# Sheet3.net
KiCad netlist of a schematic drawn in Altium Designer
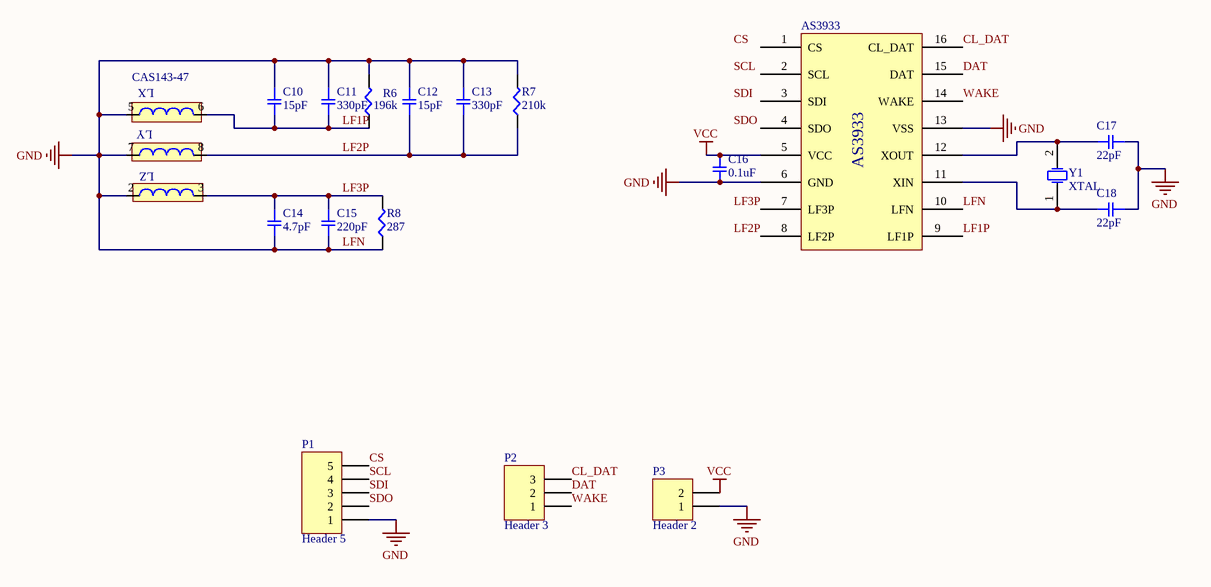
[diagram p0: Sheet3.SchDoc]

(export (version "E")
  (design (tool "Eeschema 10.0.6"))
  (components
    (comp (ref "AS3933")
      (value "~")
      (footprint "TSOP65P640X110-16N")
      (libsource (lib "AS3933") (part "Component_1"))
    )
    (comp (ref "C10")
      (value "15pF")
      (footprint "SMD-0805C")
      (description "Cap Ceramic 15pF 50V C0G 1%  0805")
      (fields (field (name "PART NUMBER") "CC0805FRNPO9BN150") (field (name "MANUFACTURER") "Yaego"))
      (libsource (lib "capacitor_0805") (part "CC0805FRNPO9BN150"))
    )
    (comp (ref "C11")
      (value "330pF")
      (footprint "SMD-0805C")
      (description "Cap Ceramic 330pF 50V C0G 2%  0805")
      (fields (field (name "PART NUMBER") "CC0805GRNPO9BN331") (field (name "MANUFACTURER") "Yageo"))
      (libsource (lib "capacitor_0805") (part "CC0805GRNPO9BN331"))
    )
    (comp (ref "C12")
      (value "15pF")
      (footprint "SMD-0805C")
      (description "Cap Ceramic 15pF 50V C0G 1%  0805")
      (fields (field (name "PART NUMBER") "CC0805FRNPO9BN150") (field (name "MANUFACTURER") "Yaego"))
      (libsource (lib "capacitor_0805") (part "CC0805FRNPO9BN150"))
    )
    (comp (ref "C13")
      (value "330pF")
      (footprint "SMD-0805C")
      (description "Cap Ceramic 330pF 50V C0G 2%  0805")
      (fields (field (name "PART NUMBER") "CC0805GRNPO9BN331") (field (name "MANUFACTURER") "Yageo"))
      (libsource (lib "capacitor_0805") (part "CC0805GRNPO9BN331"))
    )
    (comp (ref "C14")
      (value "4.7pF")
      (footprint "SMD-0805C")
      (description "Cap Ceramic 4.7pF 50V C0G 0.1pF  0805")
      (fields
        (field (name "PART NUMBER") "CL21C4R7BBANNNC")
        (field (name "MANUFACTURER") "Samsung Electro-Mechanics")
      )
      (libsource (lib "capacitor_0805") (part "CL21C4R7BBANNNC"))
    )
    (comp (ref "C15")
      (value "220pF")
      (footprint "SMD-0805C")
      (description "Cap Ceramic 220pF 100V C0G 1% 0805")
      (fields
        (field (name "PART NUMBER") "GCM2165C2A221FA16D")
        (field (name "MANUFACTURER") "Murata Manufacturing")
      )
      (libsource (lib "capacitor_0805") (part "GCM2165C2A221FA16D"))
    )
    (comp (ref "C16")
      (value "0.1uF")
      (footprint "SMD-0805C")
      (description "CAP CER 0.1uF 50V X7T 0805")
      (fields
        (field (name "PART NUMBER") "GC321AD72E103KX01D")
        (field (name "MANUFACTURER") "Samsung Electro-Mechanics")
      )
      (libsource (lib "capacitor_0805") (part "CL21B104JBCNNNC"))
    )
    (comp (ref "C17")
      (value "22pF")
      (footprint "SMD-0805C")
      (description "Cap Ceramic 22pF 50V C0G 5%0805")
      (fields
        (field (name "PART NUMBER") "CL21C220JBANNND")
        (field (name "MANUFACTURER") "Samsung Electro-Mechanics")
      )
      (libsource (lib "capacitor_0805") (part "CL21C220JBANNND"))
    )
    (comp (ref "C18")
      (value "22pF")
      (footprint "SMD-0805C")
      (description "Cap Ceramic 22pF 50V C0G 5%0805")
      (fields
        (field (name "PART NUMBER") "CL21C220JBANNND")
        (field (name "MANUFACTURER") "Samsung Electro-Mechanics")
      )
      (libsource (lib "capacitor_0805") (part "CL21C220JBANNND"))
    )
    (comp (ref "CAS143-47")
      (value "CAS143-47")
      (footprint "CAS143-47")
      (libsource (lib "CAS143-47") (part "Component_1"))
    )
    (comp (ref "P1")
      (value "Header 5")
      (footprint "HDR1X5")
      (description "Header, 5-Pin")
      (fields (field (name "PUBLISHER") "Altium Limited"))
      (libsource (lib "Miscellaneous Connectors") (part "Header 5"))
    )
    (comp (ref "P2")
      (value "Header 3")
      (footprint "HDR1X3")
      (description "Header, 3-Pin")
      (fields (field (name "PUBLISHER") "Altium Limited"))
      (libsource (lib "Miscellaneous Connectors") (part "Header 3"))
    )
    (comp (ref "P3")
      (value "Header 2")
      (footprint "HDR1X2")
      (description "Header, 2-Pin")
      (fields (field (name "PUBLISHER") "Altium Limited"))
      (libsource (lib "Miscellaneous Connectors") (part "Header 2"))
    )
    (comp (ref "R6")
      (value "196k")
      (footprint "SMD-0805-RES")
      (description "RES SMD 196K OHM 1% 1/8W 0805")
      (fields
        (field (name "PART NUMBER") "ERJ-6ENF1963V")
        (field (name "DIGI-KEY PART NUMBER") "P196KCCT-ND")
      )
      (libsource (lib "Panasonic_ERJ_0805") (part "ERJ-6ENF1963V"))
    )
    (comp (ref "R7")
      (value "210k")
      (footprint "SMD-0805-RES")
      (description "RES SMD 210K OHM 1% 1/8W 0805")
      (fields
        (field (name "PART NUMBER") "ERJ-6ENF2103V")
        (field (name "DIGI-KEY PART NUMBER") "P210KCCT-ND")
      )
      (libsource (lib "Panasonic_ERJ_0805") (part "ERJ-6ENF2103V"))
    )
    (comp (ref "R8")
      (value "287")
      (footprint "SMD-0805-RES")
      (description "RES SMD 287 OHM 1% 1/8W 0805")
      (fields (field (name "PART NUMBER") "ERJ-6ENF2870V") (field (name "DIGI-KEY PART NUMBER") "P287CCT-ND"))
      (libsource (lib "Panasonic_ERJ_0805") (part "ERJ-6ENF2870V"))
    )
    (comp (ref "Y1")
      (value "XTAL")
      (footprint "R38")
      (description "Crystal ABS07-32.768KHZ-T")
      (fields (field (name "PART NUMBER") "ABS07-32.768KHZ-T") (field (name "PUBLISHER") "Altium Limited"))
      (libsource (lib "Miscellaneous Devices") (part "XTAL"))
    )
  )
  (nets
    (net (code "1") (name "/CL_DAT") (class "Default")
      (node (ref "AS3933") (pin "16") (pinfunction "CL_DAT_16") (pintype "passive"))
      (node (ref "P2") (pin "3") (pinfunction "3_3") (pintype "passive"))
    )
    (net (code "2") (name "/CS") (class "Default")
      (node (ref "P1") (pin "5") (pinfunction "5_5") (pintype "passive"))
    )
    (net (code "3") (name "/DAT") (class "Default")
      (node (ref "AS3933") (pin "15") (pinfunction "DAT_15") (pintype "passive"))
      (node (ref "P2") (pin "2") (pinfunction "2_2") (pintype "passive"))
    )
    (net (code "4") (name "/LF1P") (class "Default")
      (node (ref "AS3933") (pin "9") (pinfunction "LF1P_9") (pintype "passive"))
      (node (ref "C10") (pin "2") (pinfunction "2_2") (pintype "passive"))
      (node (ref "C11") (pin "2") (pinfunction "2_2") (pintype "passive"))
      (node (ref "CAS143-47") (pin "6") (pinfunction "6_6") (pintype "passive"))
      (node (ref "R6") (pin "1") (pinfunction "1_1") (pintype "passive"))
    )
    (net (code "5") (name "/LF2P") (class "Default")
      (node (ref "C12") (pin "2") (pinfunction "2_2") (pintype "passive"))
      (node (ref "C13") (pin "2") (pinfunction "2_2") (pintype "passive"))
      (node (ref "CAS143-47") (pin "8") (pinfunction "8_8") (pintype "passive"))
      (node (ref "R7") (pin "1") (pinfunction "1_1") (pintype "passive"))
    )
    (net (code "6") (name "/LF3P") (class "Default")
      (node (ref "C14") (pin "1") (pinfunction "1_1") (pintype "passive"))
      (node (ref "C15") (pin "1") (pinfunction "1_1") (pintype "passive"))
      (node (ref "CAS143-47") (pin "3") (pinfunction "3_3") (pintype "passive"))
      (node (ref "R8") (pin "2") (pinfunction "2_2") (pintype "passive"))
    )
    (net (code "7") (name "/SCL") (class "Default")
      (node (ref "P1") (pin "4") (pinfunction "4_4") (pintype "passive"))
    )
    (net (code "8") (name "/SDI") (class "Default")
      (node (ref "P1") (pin "3") (pinfunction "3_3") (pintype "passive"))
    )
    (net (code "9") (name "/SDO") (class "Default")
      (node (ref "P1") (pin "2") (pinfunction "2_2") (pintype "passive"))
    )
    (net (code "10") (name "/WAKE") (class "Default")
      (node (ref "AS3933") (pin "14") (pinfunction "WAKE_14") (pintype "passive"))
      (node (ref "P2") (pin "1") (pinfunction "1_1") (pintype "passive"))
    )
    (net (code "11") (name "GND") (class "Default")
      (node (ref "AS3933") (pin "10") (pinfunction "LFN_10") (pintype "passive"))
      (node (ref "AS3933") (pin "13") (pinfunction "VSS_13") (pintype "passive"))
      (node (ref "AS3933") (pin "6") (pinfunction "GND_6") (pintype "passive"))
      (node (ref "C10") (pin "1") (pinfunction "1_1") (pintype "passive"))
      (node (ref "C11") (pin "1") (pinfunction "1_1") (pintype "passive"))
      (node (ref "C12") (pin "1") (pinfunction "1_1") (pintype "passive"))
      (node (ref "C13") (pin "1") (pinfunction "1_1") (pintype "passive"))
      (node (ref "C14") (pin "2") (pinfunction "2_2") (pintype "passive"))
      (node (ref "C15") (pin "2") (pinfunction "2_2") (pintype "passive"))
      (node (ref "C16") (pin "2") (pinfunction "2_2") (pintype "passive"))
      (node (ref "C17") (pin "1") (pinfunction "1_1") (pintype "passive"))
      (node (ref "C18") (pin "1") (pinfunction "1_1") (pintype "passive"))
      (node (ref "CAS143-47") (pin "2") (pinfunction "2_2") (pintype "passive"))
      (node (ref "CAS143-47") (pin "5") (pinfunction "5_5") (pintype "passive"))
      (node (ref "CAS143-47") (pin "7") (pinfunction "7_7") (pintype "passive"))
      (node (ref "P1") (pin "1") (pinfunction "1_1") (pintype "passive"))
      (node (ref "P3") (pin "1") (pinfunction "1_1") (pintype "passive"))
      (node (ref "R6") (pin "2") (pinfunction "2_2") (pintype "passive"))
      (node (ref "R7") (pin "2") (pinfunction "2_2") (pintype "passive"))
      (node (ref "R8") (pin "1") (pinfunction "1_1") (pintype "passive"))
    )
    (net (code "12") (name "Net-(AS3933-XIN)") (class "Default")
      (node (ref "AS3933") (pin "11") (pinfunction "XIN_11") (pintype "passive"))
      (node (ref "C18") (pin "2") (pinfunction "2_2") (pintype "passive"))
      (node (ref "Y1") (pin "1") (pinfunction "OSC1_1") (pintype "passive"))
    )
    (net (code "13") (name "Net-(AS3933-XOUT)") (class "Default")
      (node (ref "AS3933") (pin "12") (pinfunction "XOUT_12") (pintype "passive"))
      (node (ref "C17") (pin "2") (pinfunction "2_2") (pintype "passive"))
      (node (ref "Y1") (pin "2") (pinfunction "OSC2_2") (pintype "passive"))
    )
    (net (code "14") (name "VCC") (class "Default")
      (node (ref "AS3933") (pin "5") (pinfunction "VCC_5") (pintype "passive"))
      (node (ref "C16") (pin "1") (pinfunction "1_1") (pintype "passive"))
      (node (ref "P3") (pin "2") (pinfunction "2_2") (pintype "passive"))
    )
    (net (code "15") (name "unconnected-(AS3933-CS-Pad1)") (class "Default")
      (node (ref "AS3933") (pin "1") (pinfunction "CS_1") (pintype "passive"))
    )
    (net (code "16") (name "unconnected-(AS3933-LF2P-Pad8)") (class "Default")
      (node (ref "AS3933") (pin "8") (pinfunction "LF2P_8") (pintype "passive"))
    )
    (net (code "17") (name "unconnected-(AS3933-LF3P-Pad7)") (class "Default")
      (node (ref "AS3933") (pin "7") (pinfunction "LF3P_7") (pintype "passive"))
    )
    (net (code "18") (name "unconnected-(AS3933-SCL-Pad2)") (class "Default")
      (node (ref "AS3933") (pin "2") (pinfunction "SCL_2") (pintype "passive"))
    )
    (net (code "19") (name "unconnected-(AS3933-SDI-Pad3)") (class "Default")
      (node (ref "AS3933") (pin "3") (pinfunction "SDI_3") (pintype "passive"))
    )
    (net (code "20") (name "unconnected-(AS3933-SDO-Pad4)") (class "Default")
      (node (ref "AS3933") (pin "4") (pinfunction "SDO_4") (pintype "passive"))
    )
  )
)
